# ST-LINK_V2-1.net
KiCad netlist of a schematic drawn in Altium Designer
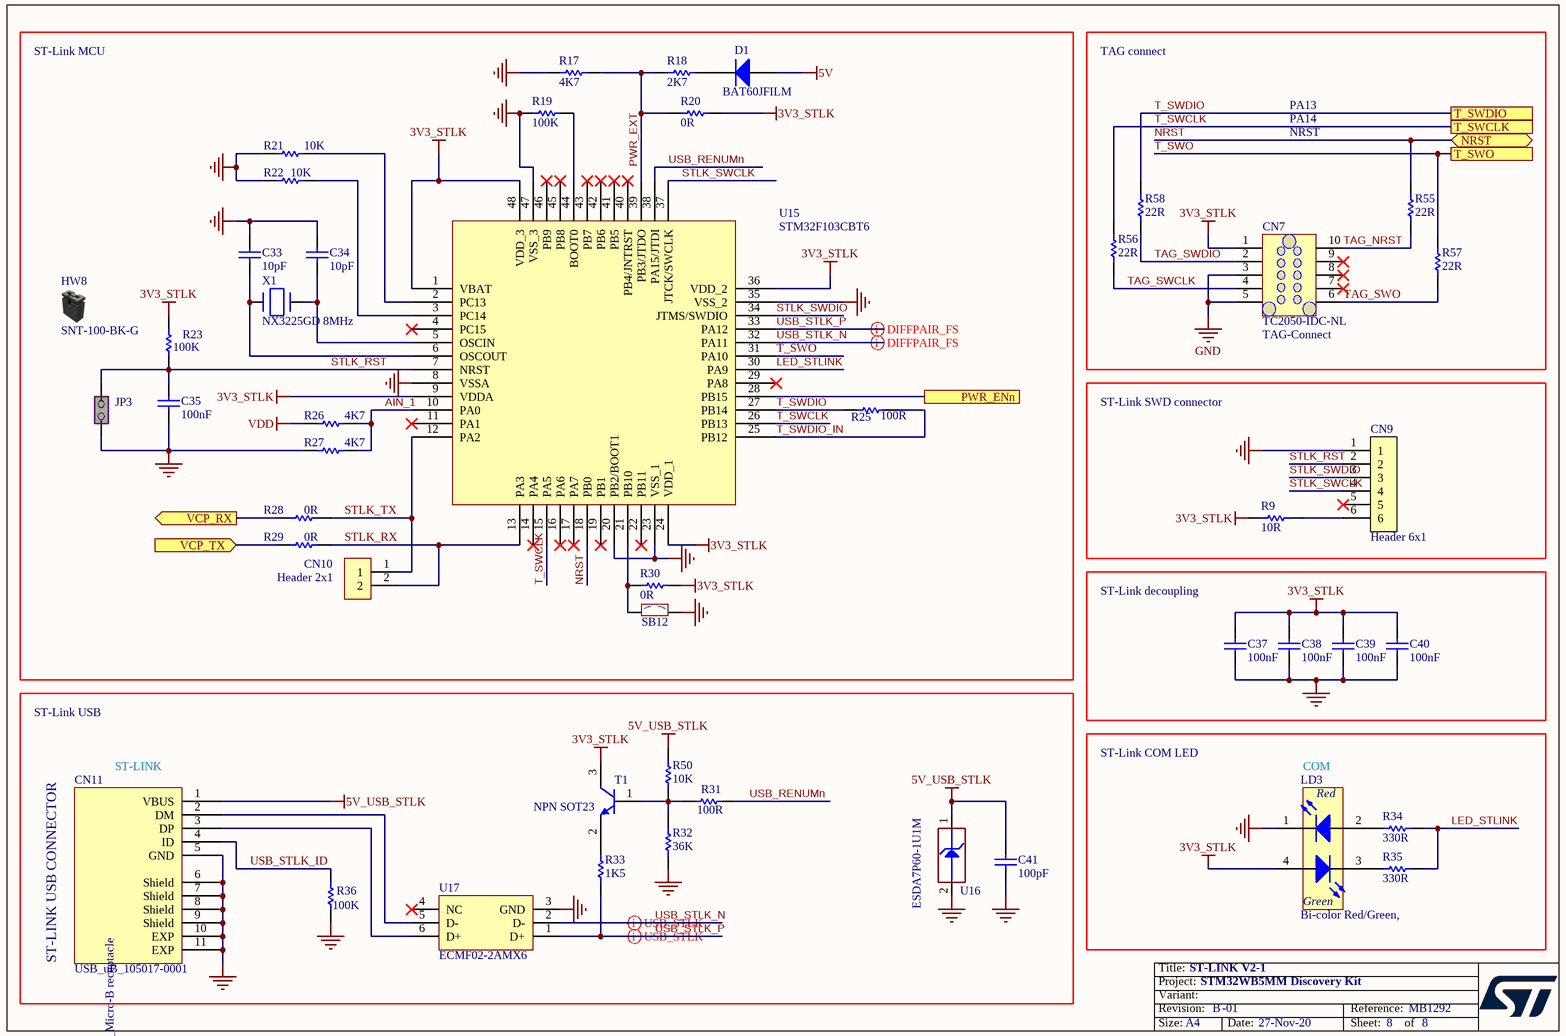
[diagram p0: ST-LINK_V2-1.SchDoc]

(export (version "E")
  (design (tool "Eeschema 10.0.6"))
  (components
    (comp (ref "C33")
      (value "10pF")
      (footprint "C0402")
      (description "Capacitor, MLCC, 10pF, 50V, NPO, +/-5%, 0402, T=0,5mm")
      (fields
        (field (name "INTERNAL_PART_NUMBER") "MCD-00015")
        (field (name "MANUFACTURER_PART_NUMBER") "CC0402JRNPO9BN100")
      )
      (libsource (lib "MCD_PARTS_database") (part "Capacitor"))
    )
    (comp (ref "C34")
      (value "10pF")
      (footprint "C0402")
      (description "Capacitor, MLCC, 10pF, 50V, NPO, +/-5%, 0402, T=0,5mm")
      (fields
        (field (name "INTERNAL_PART_NUMBER") "MCD-00015")
        (field (name "MANUFACTURER_PART_NUMBER") "CC0402JRNPO9BN100")
      )
      (libsource (lib "MCD_PARTS_database") (part "Capacitor"))
    )
    (comp (ref "C35")
      (value "100nF")
      (footprint "C0402")
      (description "Capacitor, MLCC, 100nF, 16V, X7R, +/-10%, 0402, T=0.5mm")
      (fields
        (field (name "INTERNAL_PART_NUMBER") "MCD-00006")
        (field (name "MANUFACTURER_PART_NUMBER") "CC0402KRX7R7BB104")
      )
      (libsource (lib "MCD_PARTS_database") (part "Capacitor"))
    )
    (comp (ref "C37")
      (value "100nF")
      (footprint "C0402")
      (description "Capacitor, MLCC, 100nF, 16V, X7R, +/-10%, 0402, T=0.5mm")
      (fields
        (field (name "INTERNAL_PART_NUMBER") "MCD-00006")
        (field (name "MANUFACTURER_PART_NUMBER") "CC0402KRX7R7BB104")
      )
      (libsource (lib "MCD_PARTS_database") (part "Capacitor"))
    )
    (comp (ref "C38")
      (value "100nF")
      (footprint "C0402")
      (description "Capacitor, MLCC, 100nF, 16V, X7R, +/-10%, 0402, T=0.5mm")
      (fields
        (field (name "INTERNAL_PART_NUMBER") "MCD-00006")
        (field (name "MANUFACTURER_PART_NUMBER") "CC0402KRX7R7BB104")
      )
      (libsource (lib "MCD_PARTS_database") (part "Capacitor"))
    )
    (comp (ref "C39")
      (value "100nF")
      (footprint "C0402")
      (description "Capacitor, MLCC, 100nF, 16V, X7R, +/-10%, 0402, T=0.5mm")
      (fields
        (field (name "INTERNAL_PART_NUMBER") "MCD-00006")
        (field (name "MANUFACTURER_PART_NUMBER") "CC0402KRX7R7BB104")
      )
      (libsource (lib "MCD_PARTS_database") (part "Capacitor"))
    )
    (comp (ref "C40")
      (value "100nF")
      (footprint "C0402")
      (description "Capacitor, MLCC, 100nF, 16V, X7R, +/-10%, 0402, T=0.5mm")
      (fields
        (field (name "INTERNAL_PART_NUMBER") "MCD-00006")
        (field (name "MANUFACTURER_PART_NUMBER") "CC0402KRX7R7BB104")
      )
      (libsource (lib "MCD_PARTS_database") (part "Capacitor"))
    )
    (comp (ref "C41")
      (value "100pF")
      (footprint "C0603_H0P8")
      (description "Capacitor,MLCC,100pF 50V,NPO,+/-5%, 0603,T=0,8mm")
      (fields
        (field (name "INTERNAL_PART_NUMBER") "MCD-01648")
        (field (name "MANUFACTURER_PART_NUMBER") "CC0603JRNPO9BN101")
      )
      (libsource (lib "MCD_PARTS_database") (part "Capacitor"))
    )
    (comp (ref "CN7")
      (value "TC2050-IDC-NL")
      (footprint "CON_TAG-C_TC2050-IDC-NL")
      (description "Tag_Connector Header, 10x2, No legs")
      (fields
        (field (name "INTERNAL_PART_NUMBER") "MCD-00031")
        (field (name "MANUFACTURER_PART_NUMBER") "TC2050-IDC-NL-FP")
      )
      (libsource (lib "MCD_PARTS_database") (part "Tag-10-C"))
    )
    (comp (ref "CN9")
      (value "Header 6x1")
      (footprint "CON_SAMTEC_TSW-106-14-G-S")
      (description "Header 6x1, 2,54mm, height 10.67mm")
      (fields
        (field (name "INTERNAL_PART_NUMBER") "MCD-01592")
        (field (name "MANUFACTURER_PART_NUMBER") "TSW-106-14-G-S")
      )
      (libsource (lib "MCD_PARTS_database") (part "Header 6x1"))
    )
    (comp (ref "CN10")
      (value "Header 2x1")
      (footprint "CON_SAMTEC_TSW-102-07-G-S")
      (description "Header, 2x1, 2,54mm, VR, TH, Height 5.84mm/2.54mm")
      (fields
        (field (name "INTERNAL_PART_NUMBER") "MCD-00032")
        (field (name "MANUFACTURER_PART_NUMBER") "TSW-102-07-G-S")
      )
      (libsource (lib "MCD_PARTS_database") (part "Header 2x1"))
    )
    (comp (ref "CN11")
      (value "USB_uB_105017-0001")
      (footprint "CON_USBMICROB_MOLEX_105017-0001_H2P90")
      (description "USB-MICRO-B, 0.65mm, RA, SMT, Bottom Mount,")
      (fields
        (field (name "INTERNAL_PART_NUMBER") "MCD-00028")
        (field (name "MANUFACTURER_PART_NUMBER") "1050170001")
      )
      (libsource (lib "MCD_PARTS_database") (part "USB_uB_105017.0001"))
    )
    (comp (ref "D1")
      (value "BAT60JFILM")
      (footprint "DIO_SOD323")
      (fields
        (field (name "INTERNAL_PART_NUMBER") "MCD-00034")
        (field (name "MANUFACTURER") "STMICROELECTRONICS")
        (field (name "BMS_PART_NUMBER") "9151097")
      )
      (libsource (lib "MCD_PARTS_database") (part "BAT60JFILM"))
    )
    (comp (ref "HW8")
      (value "SNT-100-BK-G")
      (description "SHUNT 2.54mm BLACK")
      (fields (field (name "INTERNAL_PART_NUMBER") "MCD-00043") (field (name "MANUFACTURER") "SAMTEC"))
      (libsource (lib "MCD_PARTS_database") (part "Shunt Black 2.54mm"))
    )
    (comp (ref "JP3")
      (value "Jumper_Header 2x1 Fitted")
      (footprint "CON_SAMTEC_TSW-102-07-G-S")
      (description "Header, 2x1, 2,54mm, VR, TH, Height 5.84mm/2.54mm - Shunt Fitted by default")
      (fields
        (field (name "INTERNAL_PART_NUMBER") "MCD-01904")
        (field (name "MANUFACTURER_PART_NUMBER") "TSW-102-07-G-S")
      )
      (libsource (lib "MCD_PARTS_database") (part "Jumper_Header 2x1 Fitted"))
    )
    (comp (ref "LD3")
      (value "Bi-color Red/Green,")
      (footprint "LED_BI-GR_HSMF-A201-A00J1")
      (description "Led, Bi-color Red/Green, 2V4, 30mA, 4-PLCC")
      (fields (field (name "INTERNAL_PART_NUMBER") "MCD-02360") (field (name "MANUFACTURER") "EVERLIGHT"))
      (libsource (lib "MCD_PARTS_database") (part "LD_BICOLOR_CMS"))
    )
    (comp (ref "R9")
      (value "10R")
      (footprint "R0402")
      (description "Resistor,10R,0402,1%,1/16W")
      (fields
        (field (name "INTERNAL_PART_NUMBER") "MCD-00358")
        (field (name "MANUFACTURER_PART_NUMBER") "RC0402FR-0710RL")
      )
      (libsource (lib "MCD_PARTS_database") (part "Resistor"))
    )
    (comp (ref "R17")
      (value "4K7")
      (footprint "R0402")
      (description "Resistor,4K7,0402,1%,1/16W")
      (fields
        (field (name "INTERNAL_PART_NUMBER") "MCD-00065")
        (field (name "MANUFACTURER_PART_NUMBER") "RC0402FR-074K7L")
      )
      (libsource (lib "MCD_PARTS_database") (part "Resistor"))
    )
    (comp (ref "R18")
      (value "2K7")
      (footprint "R0402")
      (description "Resistor,2K7,0402,1%,1/16W")
      (fields
        (field (name "INTERNAL_PART_NUMBER") "MCD-00055")
        (field (name "MANUFACTURER_PART_NUMBER") "RC0402FR-072K7L")
      )
      (libsource (lib "MCD_PARTS_database") (part "Resistor"))
    )
    (comp (ref "R19")
      (value "100K")
      (footprint "R0402")
      (description "Resistor,100K,0402,1%,1/16W")
      (fields
        (field (name "INTERNAL_PART_NUMBER") "MCD-00059")
        (field (name "MANUFACTURER_PART_NUMBER") "RC0402FR-07100KL")
      )
      (libsource (lib "MCD_PARTS_database") (part "Resistor"))
    )
    (comp (ref "R20")
      (value "0R")
      (footprint "R0402")
      (description "Resistor,0R,0402,5%,1/16W")
      (fields
        (field (name "INTERNAL_PART_NUMBER") "MCD-00052")
        (field (name "MANUFACTURER_PART_NUMBER") "RC0402JR-070RL")
      )
      (libsource (lib "MCD_PARTS_database") (part "Resistor"))
    )
    (comp (ref "R21")
      (value "10K")
      (footprint "R0402")
      (description "Resistor,10K,0402,1%,1/16W")
      (fields
        (field (name "INTERNAL_PART_NUMBER") "MCD-00053")
        (field (name "MANUFACTURER_PART_NUMBER") "RC0402FR-0710KL")
      )
      (libsource (lib "MCD_PARTS_database") (part "Resistor"))
    )
    (comp (ref "R22")
      (value "10K")
      (footprint "R0402")
      (description "Resistor,10K,0402,1%,1/16W")
      (fields
        (field (name "INTERNAL_PART_NUMBER") "MCD-00053")
        (field (name "MANUFACTURER_PART_NUMBER") "RC0402FR-0710KL")
      )
      (libsource (lib "MCD_PARTS_database") (part "Resistor"))
    )
    (comp (ref "R23")
      (value "100K")
      (footprint "R0402")
      (description "Resistor,100K,0402,1%,1/16W")
      (fields
        (field (name "INTERNAL_PART_NUMBER") "MCD-00059")
        (field (name "MANUFACTURER_PART_NUMBER") "RC0402FR-07100KL")
      )
      (libsource (lib "MCD_PARTS_database") (part "Resistor"))
    )
    (comp (ref "R25")
      (value "100R")
      (footprint "R0402")
      (description "Resistor,100R,0402,1%,1/16W")
      (fields
        (field (name "INTERNAL_PART_NUMBER") "MCD-00067")
        (field (name "MANUFACTURER_PART_NUMBER") "RC0402FR-07100RL")
      )
      (libsource (lib "MCD_PARTS_database") (part "Resistor"))
    )
    (comp (ref "R26")
      (value "4K7")
      (footprint "R0402")
      (description "Resistor,4K7,0402,1%,1/16W")
      (fields
        (field (name "INTERNAL_PART_NUMBER") "MCD-00065")
        (field (name "MANUFACTURER_PART_NUMBER") "RC0402FR-074K7L")
      )
      (libsource (lib "MCD_PARTS_database") (part "Resistor"))
    )
    (comp (ref "R27")
      (value "4K7")
      (footprint "R0402")
      (description "Resistor,4K7,0402,1%,1/16W")
      (fields
        (field (name "INTERNAL_PART_NUMBER") "MCD-00065")
        (field (name "MANUFACTURER_PART_NUMBER") "RC0402FR-074K7L")
      )
      (libsource (lib "MCD_PARTS_database") (part "Resistor"))
    )
    (comp (ref "R28")
      (value "0R")
      (footprint "R0402")
      (description "Resistor,0R,0402,5%,1/16W")
      (fields
        (field (name "INTERNAL_PART_NUMBER") "MCD-00052")
        (field (name "MANUFACTURER_PART_NUMBER") "RC0402JR-070RL")
      )
      (libsource (lib "MCD_PARTS_database") (part "Resistor"))
    )
    (comp (ref "R29")
      (value "0R")
      (footprint "R0402")
      (description "Resistor,0R,0402,5%,1/16W")
      (fields
        (field (name "INTERNAL_PART_NUMBER") "MCD-00052")
        (field (name "MANUFACTURER_PART_NUMBER") "RC0402JR-070RL")
      )
      (libsource (lib "MCD_PARTS_database") (part "Resistor"))
    )
    (comp (ref "R30")
      (value "0R")
      (footprint "R0402")
      (description "Resistor,0R,0402,5%,1/16W")
      (fields
        (field (name "INTERNAL_PART_NUMBER") "MCD-00052")
        (field (name "MANUFACTURER_PART_NUMBER") "RC0402JR-070RL")
      )
      (libsource (lib "MCD_PARTS_database") (part "Resistor"))
    )
    (comp (ref "R31")
      (value "100R")
      (footprint "R0402")
      (description "Resistor,100R,0402,1%,1/16W")
      (fields
        (field (name "INTERNAL_PART_NUMBER") "MCD-00067")
        (field (name "MANUFACTURER_PART_NUMBER") "RC0402FR-07100RL")
      )
      (libsource (lib "MCD_PARTS_database") (part "Resistor"))
    )
    (comp (ref "R32")
      (value "36K")
      (footprint "R0402")
      (description "Resistor,36K,0402,1%,1/16W")
      (fields
        (field (name "INTERNAL_PART_NUMBER") "MCD-00069")
        (field (name "MANUFACTURER_PART_NUMBER") "RC0402FR-0736KL")
      )
      (libsource (lib "MCD_PARTS_database") (part "Resistor"))
    )
    (comp (ref "R33")
      (value "1K5")
      (footprint "R0402")
      (description "Resistor,1K5,0402,1%,1/16W")
      (fields
        (field (name "INTERNAL_PART_NUMBER") "MCD-00068")
        (field (name "MANUFACTURER_PART_NUMBER") "RC0402FR-071K5L")
      )
      (libsource (lib "MCD_PARTS_database") (part "Resistor"))
    )
    (comp (ref "R34")
      (value "330R")
      (footprint "R0402")
      (description "Resistor,330R,0402,1%,1/16W")
      (fields
        (field (name "INTERNAL_PART_NUMBER") "MCD-00062")
        (field (name "MANUFACTURER_PART_NUMBER") "RC0402FR-07330RL")
      )
      (libsource (lib "MCD_PARTS_database") (part "Resistor"))
    )
    (comp (ref "R35")
      (value "330R")
      (footprint "R0402")
      (description "Resistor,330R,0402,1%,1/16W")
      (fields
        (field (name "INTERNAL_PART_NUMBER") "MCD-00062")
        (field (name "MANUFACTURER_PART_NUMBER") "RC0402FR-07330RL")
      )
      (libsource (lib "MCD_PARTS_database") (part "Resistor"))
    )
    (comp (ref "R36")
      (value "100K")
      (footprint "R0402")
      (description "Resistor,100K,0402,1%,1/16W")
      (fields
        (field (name "INTERNAL_PART_NUMBER") "MCD-00059")
        (field (name "MANUFACTURER_PART_NUMBER") "RC0402FR-07100KL")
      )
      (libsource (lib "MCD_PARTS_database") (part "Resistor"))
    )
    (comp (ref "R50")
      (value "10K")
      (footprint "R0402")
      (description "Resistor,10K,0402,1%,1/16W")
      (fields
        (field (name "INTERNAL_PART_NUMBER") "MCD-00053")
        (field (name "MANUFACTURER_PART_NUMBER") "RC0402FR-0710KL")
      )
      (libsource (lib "MCD_PARTS_database") (part "Resistor"))
    )
    (comp (ref "R55")
      (value "22R")
      (footprint "R0402")
      (description "Resistor,22R,0402,1%,1/16W")
      (fields
        (field (name "INTERNAL_PART_NUMBER") "MCD-00189")
        (field (name "MANUFACTURER_PART_NUMBER") "RC0402FR-0722RL")
      )
      (libsource (lib "MCD_PARTS_database") (part "Resistor"))
    )
    (comp (ref "R56")
      (value "22R")
      (footprint "R0402")
      (description "Resistor,22R,0402,1%,1/16W")
      (fields
        (field (name "INTERNAL_PART_NUMBER") "MCD-00189")
        (field (name "MANUFACTURER_PART_NUMBER") "RC0402FR-0722RL")
      )
      (libsource (lib "MCD_PARTS_database") (part "Resistor"))
    )
    (comp (ref "R57")
      (value "22R")
      (footprint "R0402")
      (description "Resistor,22R,0402,1%,1/16W")
      (fields
        (field (name "INTERNAL_PART_NUMBER") "MCD-00189")
        (field (name "MANUFACTURER_PART_NUMBER") "RC0402FR-0722RL")
      )
      (libsource (lib "MCD_PARTS_database") (part "Resistor"))
    )
    (comp (ref "R58")
      (value "22R")
      (footprint "R0402")
      (description "Resistor,22R,0402,1%,1/16W")
      (fields
        (field (name "INTERNAL_PART_NUMBER") "MCD-00189")
        (field (name "MANUFACTURER_PART_NUMBER") "RC0402FR-0722RL")
      )
      (libsource (lib "MCD_PARTS_database") (part "Resistor"))
    )
    (comp (ref "SB12")
      (value "SB_OFF")
      (footprint "SOLDER-BRIDGE_R0603-0R")
      (description "Solder Bridge OFF")
      (fields
        (field (name "INTERNAL_PART_NUMBER") "MCD-00072")
        (field (name "MANUFACTURER_PART_NUMBER") "RC0603JR-070RL")
      )
      (libsource (lib "MCD_PARTS_database") (part "SB_OFF"))
    )
    (comp (ref "T1")
      (value "NPN SOT23")
      (footprint "NPN_SOT23")
      (description "NPN Bipolar Transistor")
      (fields
        (field (name "INTERNAL_PART_NUMBER") "MCD-00073")
        (field (name "MANUFACTURER_PART_NUMBER") "BSR14")
      )
      (libsource (lib "MCD_PARTS_database") (part "9013-SOT23"))
    )
    (comp (ref "U15")
      (value "STM32F103CBT6")
      (footprint "ICC_LQFP48_7X7_P050")
      (description "Medium-density performance line ARM-based 32-bit MCU with 128KB Flash")
      (fields
        (field (name "INTERNAL_PART_NUMBER") "MCD-00085")
        (field (name "MANUFACTURER") "STMICROELECTRONICS")
      )
      (libsource (lib "MCD_PARTS_database") (part "STM32F103CBT6"))
    )
    (comp (ref "U16")
      (value "ESDA7P60-1U1M")
      (footprint "ESD_QFN2_1P6X1_P125")
      (description "High power transient voltage suppressor, 7V breakdown")
      (fields
        (field (name "INTERNAL_PART_NUMBER") "MCD-00251")
        (field (name "MANUFACTURER") "STMICROELECTRONICS")
      )
      (libsource (lib "MCD_PARTS_database") (part "ESD-TRANSIL"))
    )
    (comp (ref "U17")
      (value "ECMF02-2AMX6")
      (footprint "ESD_QFN-6L_1P7X1P5_P050")
      (description "Common mode filter with ESD protection for USB 2.0 interface")
      (fields
        (field (name "INTERNAL_PART_NUMBER") "MCD-00649")
        (field (name "MANUFACTURER") "STMICROELECTRONICS")
      )
      (libsource (lib "MCD_PARTS_database") (part "ECMF02-2AMX6"))
    )
    (comp (ref "X1")
      (value "NX3225GD 8MHz")
      (footprint "CRY_NX3225GD_2P")
      (description "Crystal 8MHz, 8pF, +-20ppm, 500ohms max,  SMD")
      (fields
        (field (name "INTERNAL_PART_NUMBER") "MCD-00092")
        (field (name "MANUFACTURER_PART_NUMBER") "NX3225GD 8MHz EXS00A-CG04874")
      )
      (libsource (lib "MCD_PARTS_database") (part "XTAL_2_PINS"))
    )
  )
  (nets
    (net (code "1") (name "/AIN_1") (class "Default")
      (node (ref "R26") (pin "2") (pinfunction "2_2") (pintype "passive"))
      (node (ref "R27") (pin "2") (pinfunction "2_2") (pintype "passive"))
      (node (ref "U15") (pin "10") (pinfunction "PA0_10") (pintype "passive"))
    )
    (net (code "2") (name "/LED_STLINK") (class "Default")
      (node (ref "R34") (pin "2") (pinfunction "2_2") (pintype "passive"))
      (node (ref "R35") (pin "2") (pinfunction "2_2") (pintype "passive"))
      (node (ref "U15") (pin "30") (pinfunction "PA9_30") (pintype "passive"))
    )
    (net (code "3") (name "/NRST") (class "Default")
      (node (ref "R55") (pin "2") (pinfunction "2_2") (pintype "passive"))
      (node (ref "U15") (pin "18") (pinfunction "PB0_18") (pintype "passive"))
    )
    (net (code "4") (name "/PWR_ENn") (class "Default")
      (node (ref "U15") (pin "28") (pinfunction "PB15_28") (pintype "passive"))
    )
    (net (code "5") (name "/PWR_EXT") (class "Default")
      (node (ref "R17") (pin "2") (pinfunction "2_2") (pintype "passive"))
      (node (ref "R18") (pin "1") (pinfunction "1_1") (pintype "passive"))
      (node (ref "R20") (pin "1") (pinfunction "1_1") (pintype "passive"))
      (node (ref "U15") (pin "39") (pinfunction "PB3/JTDO_39") (pintype "passive"))
    )
    (net (code "6") (name "/STLK_RST") (class "Default")
      (node (ref "C35") (pin "2") (pinfunction "2_2") (pintype "passive"))
      (node (ref "CN9") (pin "2") (pinfunction "2_2") (pintype "passive"))
      (node (ref "JP3") (pin "1") (pinfunction "COMMON_1") (pintype "passive"))
      (node (ref "R23") (pin "1") (pinfunction "1_1") (pintype "passive"))
      (node (ref "U15") (pin "7") (pinfunction "NRST_7") (pintype "passive"))
    )
    (net (code "7") (name "/STLK_RX") (class "Default")
      (node (ref "CN10") (pin "2") (pinfunction "2_2") (pintype "passive"))
      (node (ref "R29") (pin "2") (pinfunction "2_2") (pintype "passive"))
      (node (ref "U15") (pin "13") (pinfunction "PA3_13") (pintype "passive"))
    )
    (net (code "8") (name "/STLK_SWCLK") (class "Default")
      (node (ref "CN9") (pin "4") (pinfunction "4_4") (pintype "passive"))
      (node (ref "U15") (pin "37") (pinfunction "JTCK/SWCLK_37") (pintype "passive"))
    )
    (net (code "9") (name "/STLK_SWDIO") (class "Default")
      (node (ref "CN9") (pin "3") (pinfunction "3_3") (pintype "passive"))
      (node (ref "U15") (pin "34") (pinfunction "JTMS/SWDIO_34") (pintype "passive"))
    )
    (net (code "10") (name "/STLK_TX") (class "Default")
      (node (ref "CN10") (pin "1") (pinfunction "1_1") (pintype "passive"))
      (node (ref "R28") (pin "1") (pinfunction "1_1") (pintype "passive"))
      (node (ref "U15") (pin "12") (pinfunction "PA2_12") (pintype "passive"))
    )
    (net (code "11") (name "/TAG_NRST") (class "Default")
      (node (ref "CN7") (pin "10") (pinfunction "10_10") (pintype "passive"))
      (node (ref "R55") (pin "1") (pinfunction "1_1") (pintype "passive"))
    )
    (net (code "12") (name "/TAG_SWCLK") (class "Default")
      (node (ref "CN7") (pin "4") (pinfunction "4_4") (pintype "passive"))
      (node (ref "R56") (pin "1") (pinfunction "1_1") (pintype "passive"))
    )
    (net (code "13") (name "/TAG_SWDIO") (class "Default")
      (node (ref "CN7") (pin "2") (pinfunction "2_2") (pintype "passive"))
      (node (ref "R58") (pin "1") (pinfunction "1_1") (pintype "passive"))
    )
    (net (code "14") (name "/TAG_SWO") (class "Default")
      (node (ref "CN7") (pin "6") (pinfunction "6_6") (pintype "passive"))
      (node (ref "R57") (pin "2") (pinfunction "2_2") (pintype "passive"))
    )
    (net (code "15") (name "/T_SWCLK") (class "Default")
      (node (ref "R56") (pin "2") (pinfunction "2_2") (pintype "passive"))
      (node (ref "U15") (pin "15") (pinfunction "PA5_15") (pintype "passive"))
      (node (ref "U15") (pin "26") (pinfunction "PB13_26") (pintype "passive"))
    )
    (net (code "16") (name "/T_SWDIO") (class "Default")
      (node (ref "R25") (pin "1") (pinfunction "1_1") (pintype "passive"))
      (node (ref "R58") (pin "2") (pinfunction "2_2") (pintype "passive"))
      (node (ref "U15") (pin "27") (pinfunction "PB14_27") (pintype "passive"))
    )
    (net (code "17") (name "/T_SWDIO_IN") (class "Default")
      (node (ref "R25") (pin "2") (pinfunction "2_2") (pintype "passive"))
      (node (ref "U15") (pin "25") (pinfunction "PB12_25") (pintype "passive"))
    )
    (net (code "18") (name "/T_SWO") (class "Default")
      (node (ref "R57") (pin "1") (pinfunction "1_1") (pintype "passive"))
      (node (ref "U15") (pin "31") (pinfunction "PA10_31") (pintype "passive"))
    )
    (net (code "19") (name "/USB_RENUMn") (class "Default")
      (node (ref "R31") (pin "2") (pinfunction "2_2") (pintype "passive"))
      (node (ref "U15") (pin "38") (pinfunction "PA15/JTDI_38") (pintype "passive"))
    )
    (net (code "20") (name "/USB_STLK_ID") (class "Default")
      (node (ref "CN11") (pin "4") (pinfunction "ID_4") (pintype "passive"))
      (node (ref "R36") (pin "2") (pinfunction "2_2") (pintype "passive"))
    )
    (net (code "21") (name "/USB_STLK_N") (class "Default")
      (node (ref "U15") (pin "32") (pinfunction "PA11_32") (pintype "passive"))
      (node (ref "U17") (pin "2") (pinfunction "D-_2") (pintype "passive"))
    )
    (net (code "22") (name "/USB_STLK_P") (class "Default")
      (node (ref "R33") (pin "1") (pinfunction "1_1") (pintype "passive"))
      (node (ref "U15") (pin "33") (pinfunction "PA12_33") (pintype "passive"))
      (node (ref "U17") (pin "1") (pinfunction "D+_1") (pintype "passive"))
    )
    (net (code "23") (name "/VCP_RX") (class "Default")
      (node (ref "R28") (pin "2") (pinfunction "2_2") (pintype "passive"))
    )
    (net (code "24") (name "/VCP_TX") (class "Default")
      (node (ref "R29") (pin "1") (pinfunction "1_1") (pintype "passive"))
    )
    (net (code "25") (name "3V3_STLK") (class "Default")
      (node (ref "C37") (pin "2") (pinfunction "2_2") (pintype "passive"))
      (node (ref "C38") (pin "2") (pinfunction "2_2") (pintype "passive"))
      (node (ref "C39") (pin "2") (pinfunction "2_2") (pintype "passive"))
      (node (ref "C40") (pin "2") (pinfunction "2_2") (pintype "passive"))
      (node (ref "CN7") (pin "1") (pinfunction "1_1") (pintype "passive"))
      (node (ref "LD3") (pin "4") (pinfunction "YellowGreen_anode_4") (pintype "passive"))
      (node (ref "R20") (pin "2") (pinfunction "2_2") (pintype "passive"))
      (node (ref "R23") (pin "2") (pinfunction "2_2") (pintype "passive"))
      (node (ref "R30") (pin "2") (pinfunction "2_2") (pintype "passive"))
      (node (ref "R9") (pin "1") (pinfunction "1_1") (pintype "passive"))
      (node (ref "T1") (pin "3") (pinfunction "C_3") (pintype "passive"))
      (node (ref "U15") (pin "1") (pinfunction "VBAT_1") (pintype "passive"))
      (node (ref "U15") (pin "24") (pinfunction "VDD_1_24") (pintype "passive"))
      (node (ref "U15") (pin "36") (pinfunction "VDD_2_36") (pintype "passive"))
      (node (ref "U15") (pin "48") (pinfunction "VDD_3_48") (pintype "passive"))
      (node (ref "U15") (pin "9") (pinfunction "VDDA_9") (pintype "passive"))
    )
    (net (code "26") (name "5V") (class "Default")
      (node (ref "D1") (pin "1") (pinfunction "A_1") (pintype "passive"))
    )
    (net (code "27") (name "5V_USB_STLK") (class "Default")
      (node (ref "C41") (pin "1") (pinfunction "1_1") (pintype "passive"))
      (node (ref "CN11") (pin "1") (pinfunction "VBUS_1") (pintype "passive"))
      (node (ref "R50") (pin "2") (pinfunction "2_2") (pintype "passive"))
      (node (ref "U16") (pin "1") (pinfunction "IO1_1") (pintype "passive"))
    )
    (net (code "28") (name "GND") (class "Default")
      (node (ref "C33") (pin "2") (pinfunction "2_2") (pintype "passive"))
      (node (ref "C34") (pin "2") (pinfunction "2_2") (pintype "passive"))
      (node (ref "C35") (pin "1") (pinfunction "1_1") (pintype "passive"))
      (node (ref "C37") (pin "1") (pinfunction "1_1") (pintype "passive"))
      (node (ref "C38") (pin "1") (pinfunction "1_1") (pintype "passive"))
      (node (ref "C39") (pin "1") (pinfunction "1_1") (pintype "passive"))
      (node (ref "C40") (pin "1") (pinfunction "1_1") (pintype "passive"))
      (node (ref "C41") (pin "2") (pinfunction "2_2") (pintype "passive"))
      (node (ref "CN11") (pin "10") (pinfunction "EXP_10") (pintype "passive"))
      (node (ref "CN11") (pin "11") (pinfunction "EXP_11") (pintype "passive"))
      (node (ref "CN11") (pin "5") (pinfunction "GND_5") (pintype "passive"))
      (node (ref "CN11") (pin "6") (pinfunction "Shield_6") (pintype "passive"))
      (node (ref "CN11") (pin "7") (pinfunction "Shield_7") (pintype "passive"))
      (node (ref "CN11") (pin "8") (pinfunction "Shield_8") (pintype "passive"))
      (node (ref "CN11") (pin "9") (pinfunction "Shield_9") (pintype "passive"))
      (node (ref "CN7") (pin "3") (pinfunction "3_3") (pintype "passive"))
      (node (ref "CN7") (pin "5") (pinfunction "5_5") (pintype "passive"))
      (node (ref "CN9") (pin "1") (pinfunction "1_1") (pintype "passive"))
      (node (ref "JP3") (pin "2") (pinfunction "NO_2") (pintype "passive"))
      (node (ref "LD3") (pin "1") (pinfunction "RED_cathode_1") (pintype "passive"))
      (node (ref "R17") (pin "1") (pinfunction "1_1") (pintype "passive"))
      (node (ref "R19") (pin "1") (pinfunction "1_1") (pintype "passive"))
      (node (ref "R21") (pin "2") (pinfunction "2_2") (pintype "passive"))
      (node (ref "R22") (pin "1") (pinfunction "1_1") (pintype "passive"))
      (node (ref "R27") (pin "1") (pinfunction "1_1") (pintype "passive"))
      (node (ref "R32") (pin "1") (pinfunction "1_1") (pintype "passive"))
      (node (ref "R36") (pin "1") (pinfunction "1_1") (pintype "passive"))
      (node (ref "SB12") (pin "2") (pinfunction "2_2") (pintype "passive"))
      (node (ref "U15") (pin "20") (pinfunction "PB2/BOOT1_20") (pintype "passive"))
      (node (ref "U15") (pin "23") (pinfunction "VSS_1_23") (pintype "passive"))
      (node (ref "U15") (pin "35") (pinfunction "VSS_2_35") (pintype "passive"))
      (node (ref "U15") (pin "47") (pinfunction "VSS_3_47") (pintype "passive"))
      (node (ref "U15") (pin "8") (pinfunction "VSSA_8") (pintype "passive"))
      (node (ref "U16") (pin "2") (pinfunction "GND_2") (pintype "passive"))
      (node (ref "U17") (pin "3") (pinfunction "GND_3") (pintype "passive"))
    )
    (net (code "29") (name "Net-(CN9-Pad6)") (class "Default")
      (node (ref "CN9") (pin "6") (pinfunction "6_6") (pintype "passive"))
      (node (ref "R9") (pin "2") (pinfunction "2_2") (pintype "passive"))
    )
    (net (code "30") (name "Net-(CN11-DM)") (class "Default")
      (node (ref "CN11") (pin "2") (pinfunction "DM_2") (pintype "passive"))
      (node (ref "U17") (pin "5") (pinfunction "D-_5") (pintype "passive"))
    )
    (net (code "31") (name "Net-(CN11-DP)") (class "Default")
      (node (ref "CN11") (pin "3") (pinfunction "DP_3") (pintype "passive"))
      (node (ref "U17") (pin "6") (pinfunction "D+_6") (pintype "passive"))
    )
    (net (code "32") (name "Net-(D1-K)") (class "Default")
      (node (ref "D1") (pin "2") (pinfunction "K_2") (pintype "passive"))
      (node (ref "R18") (pin "2") (pinfunction "2_2") (pintype "passive"))
    )
    (net (code "33") (name "Net-(LD3-Red_anode)") (class "Default")
      (node (ref "LD3") (pin "2") (pinfunction "Red_anode_2") (pintype "passive"))
      (node (ref "R34") (pin "1") (pinfunction "1_1") (pintype "passive"))
    )
    (net (code "34") (name "Net-(LD3-YellowGreen_cathode)") (class "Default")
      (node (ref "LD3") (pin "3") (pinfunction "YellowGreen_cathode_3") (pintype "passive"))
      (node (ref "R35") (pin "1") (pinfunction "1_1") (pintype "passive"))
    )
    (net (code "35") (name "Net-(T1-B)") (class "Default")
      (node (ref "R31") (pin "1") (pinfunction "1_1") (pintype "passive"))
      (node (ref "R32") (pin "2") (pinfunction "2_2") (pintype "passive"))
      (node (ref "R50") (pin "1") (pinfunction "1_1") (pintype "passive"))
      (node (ref "T1") (pin "1") (pinfunction "B_1") (pintype "passive"))
    )
    (net (code "36") (name "Net-(T1-E)") (class "Default")
      (node (ref "R33") (pin "2") (pinfunction "2_2") (pintype "passive"))
      (node (ref "T1") (pin "2") (pinfunction "E_2") (pintype "passive"))
    )
    (net (code "37") (name "Net-(U15-BOOT0)") (class "Default")
      (node (ref "R19") (pin "2") (pinfunction "2_2") (pintype "passive"))
      (node (ref "U15") (pin "44") (pinfunction "BOOT0_44") (pintype "passive"))
    )
    (net (code "38") (name "Net-(U15-OSCIN)") (class "Default")
      (node (ref "C34") (pin "1") (pinfunction "1_1") (pintype "passive"))
      (node (ref "U15") (pin "5") (pinfunction "OSCIN_5") (pintype "passive"))
      (node (ref "X1") (pin "1") (pinfunction "X1_1") (pintype "passive"))
    )
    (net (code "39") (name "Net-(U15-OSCOUT)") (class "Default")
      (node (ref "C33") (pin "1") (pinfunction "1_1") (pintype "passive"))
      (node (ref "U15") (pin "6") (pinfunction "OSCOUT_6") (pintype "passive"))
      (node (ref "X1") (pin "2") (pinfunction "X2_2") (pintype "passive"))
    )
    (net (code "40") (name "Net-(U15-PB10)") (class "Default")
      (node (ref "R30") (pin "1") (pinfunction "1_1") (pintype "passive"))
      (node (ref "SB12") (pin "1") (pinfunction "1_1") (pintype "passive"))
      (node (ref "U15") (pin "21") (pinfunction "PB10_21") (pintype "passive"))
    )
    (net (code "41") (name "Net-(U15-PC13)") (class "Default")
      (node (ref "R21") (pin "1") (pinfunction "1_1") (pintype "passive"))
      (node (ref "U15") (pin "2") (pinfunction "PC13_2") (pintype "passive"))
    )
    (net (code "42") (name "Net-(U15-PC14)") (class "Default")
      (node (ref "R22") (pin "2") (pinfunction "2_2") (pintype "passive"))
      (node (ref "U15") (pin "3") (pinfunction "PC14_3") (pintype "passive"))
    )
    (net (code "43") (name "VDD") (class "Default")
      (node (ref "R26") (pin "1") (pinfunction "1_1") (pintype "passive"))
    )
    (net (code "44") (name "unconnected-(CN7-Pad7)") (class "Default")
      (node (ref "CN7") (pin "7") (pinfunction "7_7") (pintype "passive+no_connect"))
    )
    (net (code "45") (name "unconnected-(CN7-Pad8)") (class "Default")
      (node (ref "CN7") (pin "8") (pinfunction "8_8") (pintype "passive+no_connect"))
    )
    (net (code "46") (name "unconnected-(CN7-Pad9)") (class "Default")
      (node (ref "CN7") (pin "9") (pinfunction "9_9") (pintype "passive+no_connect"))
    )
    (net (code "47") (name "unconnected-(CN9-Pad5)") (class "Default")
      (node (ref "CN9") (pin "5") (pinfunction "5_5") (pintype "passive+no_connect"))
    )
    (net (code "48") (name "unconnected-(U15-PA1-Pad11)") (class "Default")
      (node (ref "U15") (pin "11") (pinfunction "PA1_11") (pintype "passive+no_connect"))
    )
    (net (code "49") (name "unconnected-(U15-PA4-Pad14)") (class "Default")
      (node (ref "U15") (pin "14") (pinfunction "PA4_14") (pintype "passive+no_connect"))
    )
    (net (code "50") (name "unconnected-(U15-PA6-Pad16)") (class "Default")
      (node (ref "U15") (pin "16") (pinfunction "PA6_16") (pintype "passive+no_connect"))
    )
    (net (code "51") (name "unconnected-(U15-PA7-Pad17)") (class "Default")
      (node (ref "U15") (pin "17") (pinfunction "PA7_17") (pintype "passive+no_connect"))
    )
    (net (code "52") (name "unconnected-(U15-PA8-Pad29)") (class "Default")
      (node (ref "U15") (pin "29") (pinfunction "PA8_29") (pintype "passive+no_connect"))
    )
    (net (code "53") (name "unconnected-(U15-PB1-Pad19)") (class "Default")
      (node (ref "U15") (pin "19") (pinfunction "PB1_19") (pintype "passive+no_connect"))
    )
    (net (code "54") (name "unconnected-(U15-PB4{slash}JNTRST-Pad40)") (class "Default")
      (node (ref "U15") (pin "40") (pinfunction "PB4/JNTRST_40") (pintype "passive+no_connect"))
    )
    (net (code "55") (name "unconnected-(U15-PB5-Pad41)") (class "Default")
      (node (ref "U15") (pin "41") (pinfunction "PB5_41") (pintype "passive+no_connect"))
    )
    (net (code "56") (name "unconnected-(U15-PB6-Pad42)") (class "Default")
      (node (ref "U15") (pin "42") (pinfunction "PB6_42") (pintype "passive+no_connect"))
    )
    (net (code "57") (name "unconnected-(U15-PB7-Pad43)") (class "Default")
      (node (ref "U15") (pin "43") (pinfunction "PB7_43") (pintype "passive+no_connect"))
    )
    (net (code "58") (name "unconnected-(U15-PB8-Pad45)") (class "Default")
      (node (ref "U15") (pin "45") (pinfunction "PB8_45") (pintype "passive+no_connect"))
    )
    (net (code "59") (name "unconnected-(U15-PB9-Pad46)") (class "Default")
      (node (ref "U15") (pin "46") (pinfunction "PB9_46") (pintype "passive+no_connect"))
    )
    (net (code "60") (name "unconnected-(U15-PB11-Pad22)") (class "Default")
      (node (ref "U15") (pin "22") (pinfunction "PB11_22") (pintype "passive+no_connect"))
    )
    (net (code "61") (name "unconnected-(U15-PC15-Pad4)") (class "Default")
      (node (ref "U15") (pin "4") (pinfunction "PC15_4") (pintype "passive+no_connect"))
    )
    (net (code "62") (name "unconnected-(U17-NC-Pad4)") (class "Default")
      (node (ref "U17") (pin "4") (pinfunction "NC_4") (pintype "passive+no_connect"))
    )
  )
)
